# 3_cyber60-mxhs_mcu.net
KiCad netlist of a schematic drawn in Altium Designer
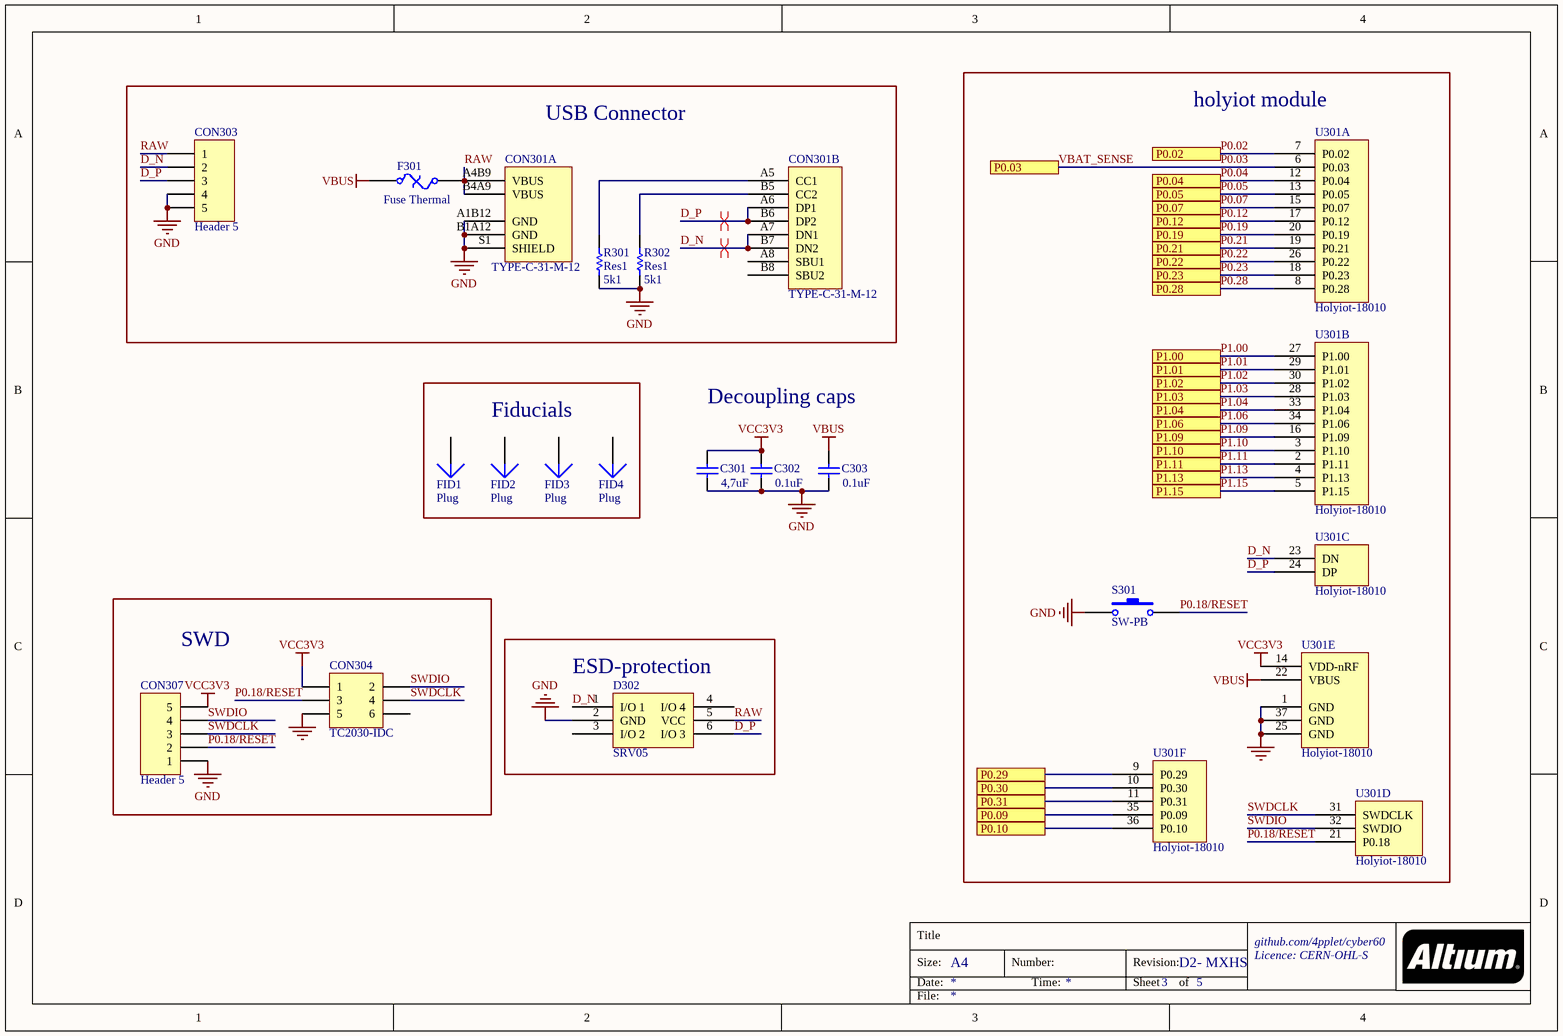
[diagram p0: 3_cyber60-mxhs_mcu.SchDoc]

(export (version "E")
  (design (tool "Eeschema 10.0.6"))
  (components
    (comp (ref "C301")
      (value "4,7uF")
      (footprint "C0603[1608]")
      (description "Capacitor")
      (fields (field (name "LCSC PART #") "C19666") (field (name "MRF.PART") "CL10A475KO8NNNC"))
      (libsource (lib "Miscellaneous Devices") (part "Cap"))
    )
    (comp (ref "C302")
      (value "0.1uF")
      (footprint "C0603[1608]")
      (description "Capacitor")
      (fields (field (name "MFG") "KEMET") (field (name "LCSC PART #") "C14663"))
      (libsource (lib "Miscellaneous Devices") (part "Cap"))
    )
    (comp (ref "C303")
      (value "0.1uF")
      (footprint "C0603[1608]")
      (description "Capacitor")
      (fields (field (name "MFG") "KEMET") (field (name "LCSC PART #") "C14663"))
      (libsource (lib "Miscellaneous Devices") (part "Cap"))
    )
    (comp (ref "CON301")
      (value "TYPE-C-31-M-12")
      (footprint "TYPE-C-31-M-12")
      (fields (field (name "MFG") "Korean Hroparts Elec") (field (name "LCSC PART #") "C165948"))
      (libsource (lib "Schlib1") (part "TYPE-C-31-M-12"))
    )
    (comp (ref "CON303")
      (value "Header 5")
      (footprint "JST SM04B-SRSS-TB")
      (description "JST for USB daughter board")
      (fields (field (name "MFG") "JST Sales America Inc.") (field (name "LCSC PART #") "C160404"))
      (libsource (lib "Miscellaneous Connectors") (part "Header 5"))
    )
    (comp (ref "CON304")
      (value "TC2030-IDC")
      (footprint "TC2030-IDC-NL")
      (description "Header, 3-Pin, Dual row")
      (libsource (lib "Miscellaneous Connectors") (part "Header 3X2"))
    )
    (comp (ref "CON307")
      (value "Header 5")
      (footprint "HDR1X5")
      (description "Header, 5-Pin")
      (libsource (lib "") (part "Header 5_1"))
    )
    (comp (ref "D302")
      (value "SRV05")
      (footprint "SOT-23-6")
      (fields (field (name "LCSC PART #") "C85364") (field (name "MRF.PART") "SRV05-4-P-T7"))
      (libsource (lib "Keebs") (part "SRV05"))
    )
    (comp (ref "F301")
      (value "Fuse Thermal")
      (footprint "C1206[3216]")
      (description "Thermal Fuse")
      (fields (field (name "MFG") "Bel Fuse Inc.") (field (name "LCSC PART #") "C135338"))
      (libsource (lib "Miscellaneous Devices") (part "Fuse Thermal"))
    )
    (comp (ref "FID1")
      (value "Plug")
      (footprint "Fiducial_Nordic")
      (libsource (lib "Miscellaneous Connectors") (part "Plug"))
    )
    (comp (ref "FID2")
      (value "Plug")
      (footprint "Fiducial_Nordic")
      (libsource (lib "Miscellaneous Connectors") (part "Plug"))
    )
    (comp (ref "FID3")
      (value "Plug")
      (footprint "Fiducial_Nordic")
      (libsource (lib "Miscellaneous Connectors") (part "Plug"))
    )
    (comp (ref "FID4")
      (value "Plug")
      (footprint "Fiducial_Nordic")
      (libsource (lib "Miscellaneous Connectors") (part "Plug"))
    )
    (comp (ref "R301")
      (value "Res1")
      (footprint "R0603[1608]")
      (description "Resistor")
      (fields
        (field (name "ALTIUM_VALUE") "5k1")
        (field (name "MFG") "Panasonic Electronic Components")
        (field (name "LCSC PART #") "C23186")
      )
      (libsource (lib "Miscellaneous Devices") (part "Res1"))
    )
    (comp (ref "R302")
      (value "Res1")
      (footprint "R0603[1608]")
      (description "Resistor")
      (fields
        (field (name "ALTIUM_VALUE") "5k1")
        (field (name "MFG") "Panasonic Electronic Components")
        (field (name "LCSC PART #") "C23186")
      )
      (libsource (lib "Miscellaneous Devices") (part "Res1"))
    )
    (comp (ref "S301")
      (value "SW-PB")
      (footprint "XKB Switch")
      (description "Switch")
      (fields (field (name "MFG") "C&K") (field (name "MRF.PART") "TS-1187A-C-D-B"))
      (libsource (lib "Miscellaneous Devices") (part "SW-PB"))
    )
    (comp (ref "U301")
      (value "Holyiot-18010")
      (footprint "Holyiot-18010 - outer pads")
      (fields (field (name "MFG") "HolyIOT"))
      (libsource (lib "Keebs") (part "Holyiot-18010"))
    )
  )
  (nets
    (net (code "1") (name "/D_N") (class "Default")
      (node (ref "CON301") (pin "A7") (pinfunction "DN1_A7") (pintype "passive"))
      (node (ref "CON301") (pin "B7") (pinfunction "DN2_B7") (pintype "passive"))
      (node (ref "CON303") (pin "2") (pinfunction "2_2") (pintype "passive"))
      (node (ref "D302") (pin "1") (pinfunction "I/O_1_1") (pintype "passive"))
      (node (ref "U301") (pin "23") (pinfunction "DN_23") (pintype "passive"))
    )
    (net (code "2") (name "/D_P") (class "Default")
      (node (ref "CON301") (pin "A6") (pinfunction "DP1_A6") (pintype "passive"))
      (node (ref "CON301") (pin "B6") (pinfunction "DP2_B6") (pintype "passive"))
      (node (ref "CON303") (pin "3") (pinfunction "3_3") (pintype "passive"))
      (node (ref "D302") (pin "6") (pinfunction "I/O_3_6") (pintype "passive"))
      (node (ref "U301") (pin "24") (pinfunction "DP_24") (pintype "passive"))
    )
    (net (code "3") (name "/P0.02") (class "Default")
      (node (ref "U301") (pin "7") (pinfunction "P0.02_7") (pintype "passive"))
    )
    (net (code "4") (name "/P0.03") (class "Default")
      (node (ref "U301") (pin "6") (pinfunction "P0.03_6") (pintype "passive"))
    )
    (net (code "5") (name "/P0.04") (class "Default")
      (node (ref "U301") (pin "12") (pinfunction "P0.04_12") (pintype "passive"))
    )
    (net (code "6") (name "/P0.05") (class "Default")
      (node (ref "U301") (pin "13") (pinfunction "P0.05_13") (pintype "passive"))
    )
    (net (code "7") (name "/P0.07") (class "Default")
      (node (ref "U301") (pin "15") (pinfunction "P0.07_15") (pintype "passive"))
    )
    (net (code "8") (name "/P0.09") (class "Default")
      (node (ref "U301") (pin "35") (pinfunction "P0.09_35") (pintype "passive"))
    )
    (net (code "9") (name "/P0.10") (class "Default")
      (node (ref "U301") (pin "36") (pinfunction "P0.10_36") (pintype "passive"))
    )
    (net (code "10") (name "/P0.12") (class "Default")
      (node (ref "U301") (pin "17") (pinfunction "P0.12_17") (pintype "passive"))
    )
    (net (code "11") (name "/P0.18{slash}RESET") (class "Default")
      (node (ref "CON304") (pin "3") (pinfunction "3_3") (pintype "passive"))
      (node (ref "CON307") (pin "2") (pinfunction "2_2") (pintype "passive"))
      (node (ref "S301") (pin "2") (pinfunction "2_2") (pintype "passive"))
      (node (ref "U301") (pin "21") (pinfunction "P0.18_21") (pintype "passive"))
    )
    (net (code "12") (name "/P0.19") (class "Default")
      (node (ref "U301") (pin "20") (pinfunction "P0.19_20") (pintype "passive"))
    )
    (net (code "13") (name "/P0.21") (class "Default")
      (node (ref "U301") (pin "19") (pinfunction "P0.21_19") (pintype "passive"))
    )
    (net (code "14") (name "/P0.22") (class "Default")
      (node (ref "U301") (pin "26") (pinfunction "P0.22_26") (pintype "passive"))
    )
    (net (code "15") (name "/P0.23") (class "Default")
      (node (ref "U301") (pin "18") (pinfunction "P0.23_18") (pintype "passive"))
    )
    (net (code "16") (name "/P0.28") (class "Default")
      (node (ref "U301") (pin "8") (pinfunction "P0.28_8") (pintype "passive"))
    )
    (net (code "17") (name "/P0.29") (class "Default")
      (node (ref "U301") (pin "9") (pinfunction "P0.29_9") (pintype "passive"))
    )
    (net (code "18") (name "/P0.30") (class "Default")
      (node (ref "U301") (pin "10") (pinfunction "P0.30_10") (pintype "passive"))
    )
    (net (code "19") (name "/P0.31") (class "Default")
      (node (ref "U301") (pin "11") (pinfunction "P0.31_11") (pintype "passive"))
    )
    (net (code "20") (name "/P1.00") (class "Default")
      (node (ref "U301") (pin "27") (pinfunction "P1.00_27") (pintype "passive"))
    )
    (net (code "21") (name "/P1.01") (class "Default")
      (node (ref "U301") (pin "29") (pinfunction "P1.01_29") (pintype "passive"))
    )
    (net (code "22") (name "/P1.02") (class "Default")
      (node (ref "U301") (pin "30") (pinfunction "P1.02_30") (pintype "passive"))
    )
    (net (code "23") (name "/P1.03") (class "Default")
      (node (ref "U301") (pin "28") (pinfunction "P1.03_28") (pintype "passive"))
    )
    (net (code "24") (name "/P1.04") (class "Default")
      (node (ref "U301") (pin "33") (pinfunction "P1.04_33") (pintype "passive"))
    )
    (net (code "25") (name "/P1.06") (class "Default")
      (node (ref "U301") (pin "34") (pinfunction "P1.06_34") (pintype "passive"))
    )
    (net (code "26") (name "/P1.09") (class "Default")
      (node (ref "U301") (pin "16") (pinfunction "P1.09_16") (pintype "passive"))
    )
    (net (code "27") (name "/P1.10") (class "Default")
      (node (ref "U301") (pin "3") (pinfunction "P1.10_3") (pintype "passive"))
    )
    (net (code "28") (name "/P1.11") (class "Default")
      (node (ref "U301") (pin "2") (pinfunction "P1.11_2") (pintype "passive"))
    )
    (net (code "29") (name "/P1.13") (class "Default")
      (node (ref "U301") (pin "4") (pinfunction "P1.13_4") (pintype "passive"))
    )
    (net (code "30") (name "/P1.15") (class "Default")
      (node (ref "U301") (pin "5") (pinfunction "P1.15_5") (pintype "passive"))
    )
    (net (code "31") (name "/RAW") (class "Default")
      (node (ref "CON301") (pin "A4B9") (pinfunction "VBUS_A4B9") (pintype "passive"))
      (node (ref "CON301") (pin "B4A9") (pinfunction "VBUS_B4A9") (pintype "passive"))
      (node (ref "CON303") (pin "1") (pinfunction "1_1") (pintype "passive"))
      (node (ref "D302") (pin "5") (pinfunction "VCC_5") (pintype "passive"))
      (node (ref "F301") (pin "2") (pinfunction "2_2") (pintype "passive"))
    )
    (net (code "32") (name "/SWDCLK") (class "Default")
      (node (ref "CON304") (pin "4") (pinfunction "4_4") (pintype "passive"))
      (node (ref "CON307") (pin "3") (pinfunction "3_3") (pintype "passive"))
      (node (ref "U301") (pin "31") (pinfunction "SWDCLK_31") (pintype "passive"))
    )
    (net (code "33") (name "/SWDIO") (class "Default")
      (node (ref "CON304") (pin "2") (pinfunction "2_2") (pintype "passive"))
      (node (ref "CON307") (pin "4") (pinfunction "4_4") (pintype "passive"))
      (node (ref "U301") (pin "32") (pinfunction "SWDIO_32") (pintype "passive"))
    )
    (net (code "34") (name "GND") (class "Default")
      (node (ref "C301") (pin "1") (pinfunction "1_1") (pintype "passive"))
      (node (ref "C302") (pin "1") (pinfunction "1_1") (pintype "passive"))
      (node (ref "C303") (pin "1") (pinfunction "1_1") (pintype "passive"))
      (node (ref "CON301") (pin "A1B12") (pinfunction "GND_A1B12") (pintype "passive"))
      (node (ref "CON301") (pin "B1A12") (pinfunction "GND_B1A12") (pintype "passive"))
      (node (ref "CON301") (pin "S1") (pinfunction "SHIELD_S1") (pintype "passive"))
      (node (ref "CON303") (pin "4") (pinfunction "4_4") (pintype "passive"))
      (node (ref "CON303") (pin "5") (pinfunction "5_5") (pintype "passive"))
      (node (ref "CON304") (pin "5") (pinfunction "5_5") (pintype "passive"))
      (node (ref "CON307") (pin "1") (pinfunction "1_1") (pintype "passive"))
      (node (ref "D302") (pin "2") (pinfunction "GND_2") (pintype "passive"))
      (node (ref "R301") (pin "2") (pinfunction "2_2") (pintype "passive"))
      (node (ref "R302") (pin "2") (pinfunction "2_2") (pintype "passive"))
      (node (ref "S301") (pin "1") (pinfunction "1_1") (pintype "passive"))
      (node (ref "U301") (pin "1") (pinfunction "GND_1") (pintype "passive"))
      (node (ref "U301") (pin "25") (pinfunction "GND_25") (pintype "passive"))
      (node (ref "U301") (pin "37") (pinfunction "GND_37") (pintype "passive"))
    )
    (net (code "35") (name "Net-(CON301B-CC1)") (class "Default")
      (node (ref "CON301") (pin "A5") (pinfunction "CC1_A5") (pintype "passive"))
      (node (ref "R301") (pin "1") (pinfunction "1_1") (pintype "passive"))
    )
    (net (code "36") (name "Net-(CON301B-CC2)") (class "Default")
      (node (ref "CON301") (pin "B5") (pinfunction "CC2_B5") (pintype "passive"))
      (node (ref "R302") (pin "1") (pinfunction "1_1") (pintype "passive"))
    )
    (net (code "37") (name "VBUS") (class "Default")
      (node (ref "C303") (pin "2") (pinfunction "2_2") (pintype "passive"))
      (node (ref "F301") (pin "1") (pinfunction "1_1") (pintype "passive"))
      (node (ref "U301") (pin "22") (pinfunction "VBUS_22") (pintype "passive"))
    )
    (net (code "38") (name "VCC3V3") (class "Default")
      (node (ref "C301") (pin "2") (pinfunction "2_2") (pintype "passive"))
      (node (ref "C302") (pin "2") (pinfunction "2_2") (pintype "passive"))
      (node (ref "CON304") (pin "1") (pinfunction "1_1") (pintype "passive"))
      (node (ref "CON307") (pin "5") (pinfunction "5_5") (pintype "passive"))
      (node (ref "U301") (pin "14") (pinfunction "VDD-nRF_14") (pintype "passive"))
    )
    (net (code "39") (name "unconnected-(CON301B-SBU1-PadA8)") (class "Default")
      (node (ref "CON301") (pin "A8") (pinfunction "SBU1_A8") (pintype "passive"))
    )
    (net (code "40") (name "unconnected-(CON301B-SBU2-PadB8)") (class "Default")
      (node (ref "CON301") (pin "B8") (pinfunction "SBU2_B8") (pintype "passive"))
    )
    (net (code "41") (name "unconnected-(CON304-Pad6)") (class "Default")
      (node (ref "CON304") (pin "6") (pinfunction "6_6") (pintype "passive"))
    )
    (net (code "42") (name "unconnected-(D302-I{slash}O_2-Pad3)") (class "Default")
      (node (ref "D302") (pin "3") (pinfunction "I/O_2_3") (pintype "passive"))
    )
    (net (code "43") (name "unconnected-(D302-I{slash}O_4-Pad4)") (class "Default")
      (node (ref "D302") (pin "4") (pinfunction "I/O_4_4") (pintype "passive"))
    )
    (net (code "44") (name "unconnected-(FID1-Pad1)") (class "Default")
      (node (ref "FID1") (pin "1") (pinfunction "1_1") (pintype "passive"))
    )
    (net (code "45") (name "unconnected-(FID2-Pad1)") (class "Default")
      (node (ref "FID2") (pin "1") (pinfunction "1_1") (pintype "passive"))
    )
    (net (code "46") (name "unconnected-(FID3-Pad1)") (class "Default")
      (node (ref "FID3") (pin "1") (pinfunction "1_1") (pintype "passive"))
    )
    (net (code "47") (name "unconnected-(FID4-Pad1)") (class "Default")
      (node (ref "FID4") (pin "1") (pinfunction "1_1") (pintype "passive"))
    )
  )
)
